# Filters.net
KiCad netlist of a schematic drawn in Altium Designer
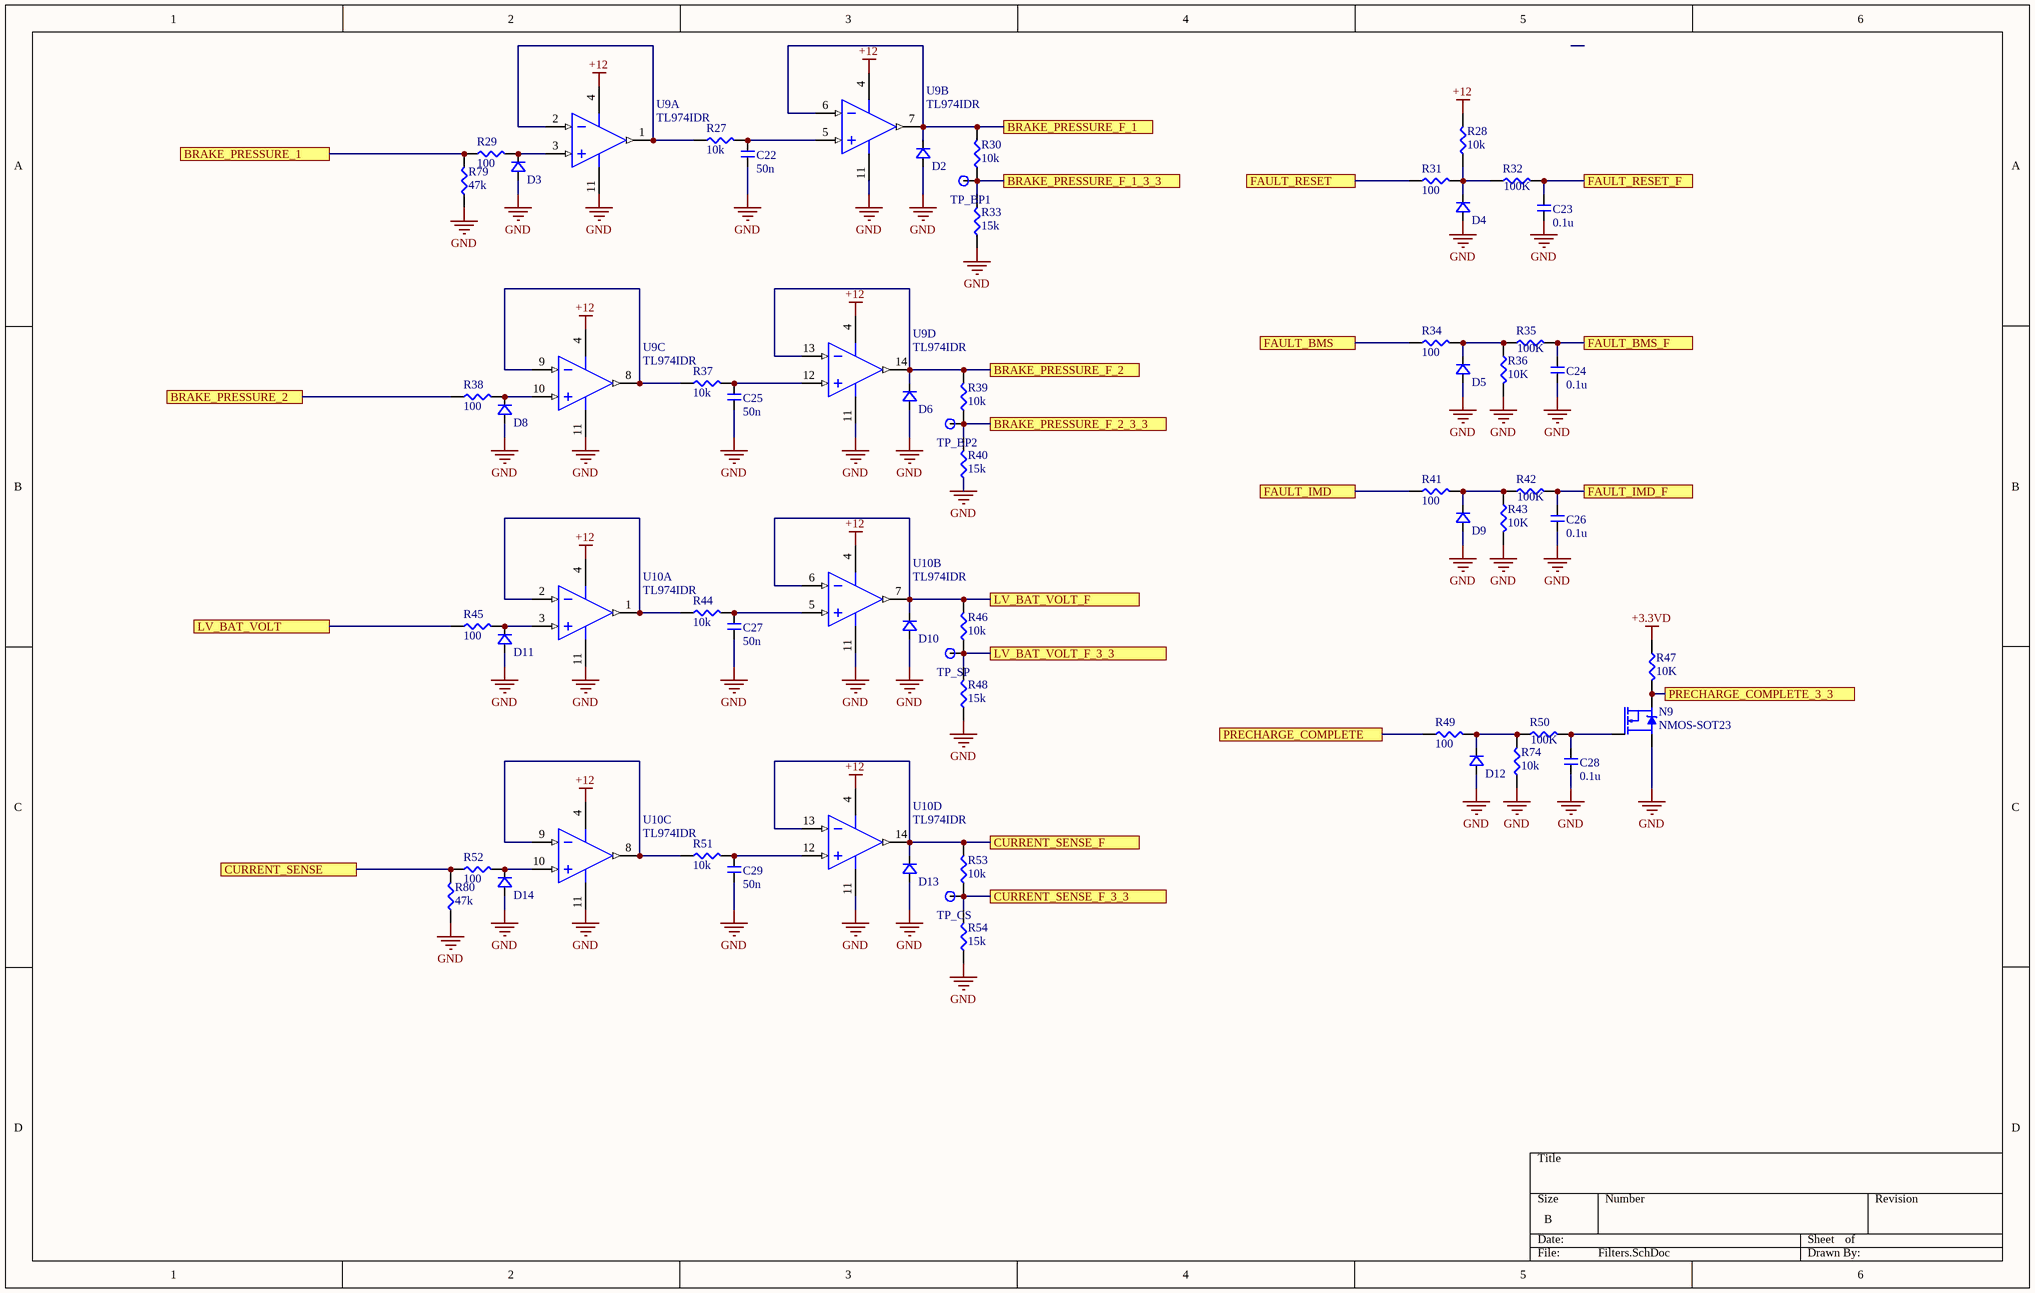
[diagram p0: Filters.SchDoc]

(export (version "E")
  (design (tool "Eeschema 10.0.6"))
  (components
    (comp (ref "C22")
      (value "50n")
      (footprint "CAP-0603")
      (libsource (lib "ife19_Elec_Library") (part "CAP-0603"))
    )
    (comp (ref "C23")
      (value "0.1u")
      (footprint "CAP-0603")
      (libsource (lib "ife19_Elec_Library") (part "CAP-0603"))
    )
    (comp (ref "C24")
      (value "0.1u")
      (footprint "CAP-0603")
      (libsource (lib "ife19_Elec_Library") (part "CAP-0603"))
    )
    (comp (ref "C25")
      (value "50n")
      (footprint "CAP-0603")
      (libsource (lib "ife19_Elec_Library") (part "CAP-0603"))
    )
    (comp (ref "C26")
      (value "0.1u")
      (footprint "CAP-0603")
      (libsource (lib "ife19_Elec_Library") (part "CAP-0603"))
    )
    (comp (ref "C27")
      (value "50n")
      (footprint "CAP-0603")
      (libsource (lib "ife19_Elec_Library") (part "CAP-0603"))
    )
    (comp (ref "C28")
      (value "0.1u")
      (footprint "CAP-0603")
      (libsource (lib "ife19_Elec_Library") (part "CAP-0603"))
    )
    (comp (ref "C29")
      (value "50n")
      (footprint "CAP-0603")
      (libsource (lib "ife19_Elec_Library") (part "CAP-0603"))
    )
    (comp (ref "D2")
      (value "5V ZENER")
      (footprint "SOD123")
      (libsource (lib "ife19_Elec_Library") (part "DIODE-SOD123"))
    )
    (comp (ref "D3")
      (value "12V ZENER")
      (footprint "ife19_Elec_Library:SOD123")
      (libsource (lib "ife19_Elec_Library") (part "DIODE-SOD123"))
    )
    (comp (ref "D4")
      (value "12V ZENER")
      (footprint "SOD123")
      (libsource (lib "ife19_Elec_Library") (part "DIODE-SOD123"))
    )
    (comp (ref "D5")
      (value "12V ZENER")
      (footprint "SOD123")
      (libsource (lib "ife19_Elec_Library") (part "DIODE-SOD123"))
    )
    (comp (ref "D6")
      (value "5V ZENER")
      (footprint "SOD123")
      (libsource (lib "ife19_Elec_Library") (part "DIODE-SOD123"))
    )
    (comp (ref "D8")
      (value "12V ZENER")
      (footprint "SOD123")
      (libsource (lib "ife19_Elec_Library") (part "DIODE-SOD123"))
    )
    (comp (ref "D9")
      (value "12V ZENER")
      (footprint "SOD123")
      (libsource (lib "ife19_Elec_Library") (part "DIODE-SOD123"))
    )
    (comp (ref "D10")
      (value "5V ZENER")
      (footprint "SOD123")
      (libsource (lib "ife19_Elec_Library") (part "DIODE-SOD123"))
    )
    (comp (ref "D11")
      (value "12V ZENER")
      (footprint "SOD123")
      (libsource (lib "ife19_Elec_Library") (part "DIODE-SOD123"))
    )
    (comp (ref "D12")
      (value "12V ZENER")
      (footprint "SOD123")
      (libsource (lib "ife19_Elec_Library") (part "DIODE-SOD123"))
    )
    (comp (ref "D13")
      (value "5V ZENER")
      (footprint "SOD123")
      (libsource (lib "ife19_Elec_Library") (part "DIODE-SOD123"))
    )
    (comp (ref "D14")
      (value "12V ZENER")
      (footprint "SOD123")
      (libsource (lib "ife19_Elec_Library") (part "DIODE-SOD123"))
    )
    (comp (ref "N9")
      (value "NMOS-SOT23")
      (footprint "SOT23")
      (libsource (lib "ife19_Elec_Library") (part "NMOS-SOT23"))
    )
    (comp (ref "R27")
      (value "10k")
      (footprint "RES-0603")
      (libsource (lib "ife19_Elec_Library") (part "RES-0603"))
    )
    (comp (ref "R28")
      (value "10k")
      (footprint "RES-0603")
      (libsource (lib "ife19_Elec_Library") (part "RES-0603"))
    )
    (comp (ref "R29")
      (value "100")
      (footprint "RES-0603")
      (libsource (lib "ife19_Elec_Library") (part "RES-0603"))
    )
    (comp (ref "R30")
      (value "10k")
      (footprint "RES-0603")
      (libsource (lib "ife19_Elec_Library") (part "RES-0603"))
    )
    (comp (ref "R31")
      (value "100")
      (footprint "RES-0603")
      (libsource (lib "ife19_Elec_Library") (part "RES-0603"))
    )
    (comp (ref "R32")
      (value "100K")
      (footprint "RES-0603")
      (libsource (lib "ife19_Elec_Library") (part "RES-0603"))
    )
    (comp (ref "R33")
      (value "15k")
      (footprint "RES-0603")
      (libsource (lib "ife19_Elec_Library") (part "RES-0603"))
    )
    (comp (ref "R34")
      (value "100")
      (footprint "RES-0603")
      (libsource (lib "ife19_Elec_Library") (part "RES-0603"))
    )
    (comp (ref "R35")
      (value "100K")
      (footprint "RES-0603")
      (libsource (lib "ife19_Elec_Library") (part "RES-0603"))
    )
    (comp (ref "R36")
      (value "10K")
      (footprint "RES-0603")
      (libsource (lib "ife19_Elec_Library") (part "RES-0603"))
    )
    (comp (ref "R37")
      (value "10k")
      (footprint "RES-0603")
      (libsource (lib "ife19_Elec_Library") (part "RES-0603"))
    )
    (comp (ref "R38")
      (value "100")
      (footprint "RES-0603")
      (libsource (lib "ife19_Elec_Library") (part "RES-0603"))
    )
    (comp (ref "R39")
      (value "10k")
      (footprint "RES-0603")
      (libsource (lib "ife19_Elec_Library") (part "RES-0603"))
    )
    (comp (ref "R40")
      (value "15k")
      (footprint "RES-0603")
      (libsource (lib "ife19_Elec_Library") (part "RES-0603"))
    )
    (comp (ref "R41")
      (value "100")
      (footprint "RES-0603")
      (libsource (lib "ife19_Elec_Library") (part "RES-0603"))
    )
    (comp (ref "R42")
      (value "100K")
      (footprint "RES-0603")
      (libsource (lib "ife19_Elec_Library") (part "RES-0603"))
    )
    (comp (ref "R43")
      (value "10K")
      (footprint "RES-0603")
      (libsource (lib "ife19_Elec_Library") (part "RES-0603"))
    )
    (comp (ref "R44")
      (value "10k")
      (footprint "RES-0603")
      (libsource (lib "ife19_Elec_Library") (part "RES-0603"))
    )
    (comp (ref "R45")
      (value "100")
      (footprint "RES-0603")
      (libsource (lib "ife19_Elec_Library") (part "RES-0603"))
    )
    (comp (ref "R46")
      (value "10k")
      (footprint "RES-0603")
      (libsource (lib "ife19_Elec_Library") (part "RES-0603"))
    )
    (comp (ref "R47")
      (value "10K")
      (footprint "RES-0603")
      (libsource (lib "ife19_Elec_Library") (part "RES-0603"))
    )
    (comp (ref "R48")
      (value "15k")
      (footprint "RES-0603")
      (libsource (lib "ife19_Elec_Library") (part "RES-0603"))
    )
    (comp (ref "R49")
      (value "100")
      (footprint "RES-0603")
      (libsource (lib "ife19_Elec_Library") (part "RES-0603"))
    )
    (comp (ref "R50")
      (value "100K")
      (footprint "RES-0603")
      (libsource (lib "ife19_Elec_Library") (part "RES-0603"))
    )
    (comp (ref "R51")
      (value "10k")
      (footprint "RES-0603")
      (libsource (lib "ife19_Elec_Library") (part "RES-0603"))
    )
    (comp (ref "R52")
      (value "100")
      (footprint "RES-0603")
      (libsource (lib "ife19_Elec_Library") (part "RES-0603"))
    )
    (comp (ref "R53")
      (value "10k")
      (footprint "RES-0603")
      (libsource (lib "ife19_Elec_Library") (part "RES-0603"))
    )
    (comp (ref "R54")
      (value "15k")
      (footprint "RES-0603")
      (libsource (lib "ife19_Elec_Library") (part "RES-0603"))
    )
    (comp (ref "R74")
      (value "10k")
      (footprint "RES-0603")
      (libsource (lib "ife19_Elec_Library") (part "RES-0603"))
    )
    (comp (ref "R79")
      (value "47k")
      (footprint "RES-0603")
      (libsource (lib "ife19_Elec_Library") (part "RES-0603"))
    )
    (comp (ref "R80")
      (value "47k")
      (footprint "RES-0603")
      (libsource (lib "ife19_Elec_Library") (part "RES-0603"))
    )
    (comp (ref "TP_BP1")
      (value "~")
      (footprint "Testpoint")
      (libsource (lib "ife19_Elec_Library") (part "Testpoint"))
    )
    (comp (ref "TP_BP2")
      (value "~")
      (footprint "Testpoint")
      (libsource (lib "ife19_Elec_Library") (part "Testpoint"))
    )
    (comp (ref "TP_CS")
      (value "~")
      (footprint "Testpoint")
      (libsource (lib "ife19_Elec_Library") (part "Testpoint"))
    )
    (comp (ref "TP_SP")
      (value "~")
      (footprint "Testpoint")
      (libsource (lib "ife19_Elec_Library") (part "Testpoint"))
    )
    (comp (ref "U9")
      (value "TL974IDR")
      (footprint "D0014A_M")
      (fields (field (name "MANUFACTURER") "Texas Instruments"))
      (libsource (lib "Altium Content Vault") (part "TI-TLXX4X_MC3403-X14"))
    )
    (comp (ref "U10")
      (value "TL974IDR")
      (footprint "D0014A_M")
      (fields (field (name "MANUFACTURER") "Texas Instruments"))
      (libsource (lib "Altium Content Vault") (part "TI-TLXX4X_MC3403-X14"))
    )
  )
  (nets
    (net (code "1") (name "+3.3VD") (class "Default")
      (node (ref "R47") (pin "1") (pinfunction "1_1") (pintype "passive"))
    )
    (net (code "2") (name "+12") (class "Default")
      (node (ref "R28") (pin "2") (pinfunction "2_2") (pintype "passive"))
      (node (ref "U10") (pin "4") (pinfunction "VCC+_4") (pintype "power_in"))
      (node (ref "U9") (pin "4") (pinfunction "VCC+_4") (pintype "power_in"))
    )
    (net (code "3") (name "/BRAKE_PRESSURE_1") (class "Default")
      (node (ref "R29") (pin "1") (pinfunction "1_1") (pintype "passive"))
      (node (ref "R79") (pin "2") (pinfunction "2_2") (pintype "passive"))
    )
    (net (code "4") (name "/BRAKE_PRESSURE_2") (class "Default")
      (node (ref "R38") (pin "1") (pinfunction "1_1") (pintype "passive"))
    )
    (net (code "5") (name "/BRAKE_PRESSURE_F_1") (class "Default")
      (node (ref "D2") (pin "K") (pinfunction "K_K") (pintype "passive"))
      (node (ref "R30") (pin "2") (pinfunction "2_2") (pintype "passive"))
      (node (ref "U9") (pin "6") (pinfunction "IN2-_6") (pintype "input"))
      (node (ref "U9") (pin "7") (pinfunction "OUT2_7") (pintype "output"))
    )
    (net (code "6") (name "/BRAKE_PRESSURE_F_1_3_3") (class "Default")
      (node (ref "R30") (pin "1") (pinfunction "1_1") (pintype "passive"))
      (node (ref "R33") (pin "2") (pinfunction "2_2") (pintype "passive"))
      (node (ref "TP_BP1") (pin "1") (pinfunction "1_1") (pintype "passive"))
    )
    (net (code "7") (name "/BRAKE_PRESSURE_F_2") (class "Default")
      (node (ref "D6") (pin "K") (pinfunction "K_K") (pintype "passive"))
      (node (ref "R39") (pin "2") (pinfunction "2_2") (pintype "passive"))
      (node (ref "U9") (pin "13") (pinfunction "IN4-_13") (pintype "input"))
      (node (ref "U9") (pin "14") (pinfunction "OUT4_14") (pintype "output"))
    )
    (net (code "8") (name "/BRAKE_PRESSURE_F_2_3_3") (class "Default")
      (node (ref "R39") (pin "1") (pinfunction "1_1") (pintype "passive"))
      (node (ref "R40") (pin "2") (pinfunction "2_2") (pintype "passive"))
      (node (ref "TP_BP2") (pin "1") (pinfunction "1_1") (pintype "passive"))
    )
    (net (code "9") (name "/CURRENT_SENSE") (class "Default")
      (node (ref "R52") (pin "1") (pinfunction "1_1") (pintype "passive"))
      (node (ref "R80") (pin "2") (pinfunction "2_2") (pintype "passive"))
    )
    (net (code "10") (name "/CURRENT_SENSE_F") (class "Default")
      (node (ref "D13") (pin "K") (pinfunction "K_K") (pintype "passive"))
      (node (ref "R53") (pin "2") (pinfunction "2_2") (pintype "passive"))
      (node (ref "U10") (pin "13") (pinfunction "IN4-_13") (pintype "input"))
      (node (ref "U10") (pin "14") (pinfunction "OUT4_14") (pintype "output"))
    )
    (net (code "11") (name "/CURRENT_SENSE_F_3_3") (class "Default")
      (node (ref "R53") (pin "1") (pinfunction "1_1") (pintype "passive"))
      (node (ref "R54") (pin "2") (pinfunction "2_2") (pintype "passive"))
      (node (ref "TP_CS") (pin "1") (pinfunction "1_1") (pintype "passive"))
    )
    (net (code "12") (name "/FAULT_BMS") (class "Default")
      (node (ref "R34") (pin "1") (pinfunction "1_1") (pintype "passive"))
    )
    (net (code "13") (name "/FAULT_BMS_F") (class "Default")
      (node (ref "C24") (pin "2") (pinfunction "2_2") (pintype "passive"))
      (node (ref "R35") (pin "2") (pinfunction "2_2") (pintype "passive"))
    )
    (net (code "14") (name "/FAULT_IMD") (class "Default")
      (node (ref "R41") (pin "1") (pinfunction "1_1") (pintype "passive"))
    )
    (net (code "15") (name "/FAULT_IMD_F") (class "Default")
      (node (ref "C26") (pin "2") (pinfunction "2_2") (pintype "passive"))
      (node (ref "R42") (pin "2") (pinfunction "2_2") (pintype "passive"))
    )
    (net (code "16") (name "/FAULT_RESET") (class "Default")
      (node (ref "R31") (pin "1") (pinfunction "1_1") (pintype "passive"))
    )
    (net (code "17") (name "/FAULT_RESET_F") (class "Default")
      (node (ref "C23") (pin "2") (pinfunction "2_2") (pintype "passive"))
      (node (ref "R32") (pin "2") (pinfunction "2_2") (pintype "passive"))
    )
    (net (code "18") (name "/LV_BAT_VOLT") (class "Default")
      (node (ref "R45") (pin "1") (pinfunction "1_1") (pintype "passive"))
    )
    (net (code "19") (name "/LV_BAT_VOLT_F") (class "Default")
      (node (ref "D10") (pin "K") (pinfunction "K_K") (pintype "passive"))
      (node (ref "R46") (pin "2") (pinfunction "2_2") (pintype "passive"))
      (node (ref "U10") (pin "6") (pinfunction "IN2-_6") (pintype "input"))
      (node (ref "U10") (pin "7") (pinfunction "OUT2_7") (pintype "output"))
    )
    (net (code "20") (name "/LV_BAT_VOLT_F_3_3") (class "Default")
      (node (ref "R46") (pin "1") (pinfunction "1_1") (pintype "passive"))
      (node (ref "R48") (pin "2") (pinfunction "2_2") (pintype "passive"))
      (node (ref "TP_SP") (pin "1") (pinfunction "1_1") (pintype "passive"))
    )
    (net (code "21") (name "/PRECHARGE_COMPLETE") (class "Default")
      (node (ref "R49") (pin "1") (pinfunction "1_1") (pintype "passive"))
    )
    (net (code "22") (name "/PRECHARGE_COMPLETE_3_3") (class "Default")
      (node (ref "N9") (pin "3") (pinfunction "D_3") (pintype "passive"))
      (node (ref "R47") (pin "2") (pinfunction "2_2") (pintype "passive"))
    )
    (net (code "23") (name "GND") (class "Default")
      (node (ref "C22") (pin "1") (pinfunction "1_1") (pintype "passive"))
      (node (ref "C23") (pin "1") (pinfunction "1_1") (pintype "passive"))
      (node (ref "C24") (pin "1") (pinfunction "1_1") (pintype "passive"))
      (node (ref "C25") (pin "1") (pinfunction "1_1") (pintype "passive"))
      (node (ref "C26") (pin "1") (pinfunction "1_1") (pintype "passive"))
      (node (ref "C27") (pin "1") (pinfunction "1_1") (pintype "passive"))
      (node (ref "C28") (pin "1") (pinfunction "1_1") (pintype "passive"))
      (node (ref "C29") (pin "1") (pinfunction "1_1") (pintype "passive"))
      (node (ref "D10") (pin "A") (pinfunction "A_A") (pintype "passive"))
      (node (ref "D11") (pin "A") (pinfunction "A_A") (pintype "passive"))
      (node (ref "D12") (pin "A") (pinfunction "A_A") (pintype "passive"))
      (node (ref "D13") (pin "A") (pinfunction "A_A") (pintype "passive"))
      (node (ref "D14") (pin "A") (pinfunction "A_A") (pintype "passive"))
      (node (ref "D2") (pin "A") (pinfunction "A_A") (pintype "passive"))
      (node (ref "D3") (pin "A") (pinfunction "A_A") (pintype "passive"))
      (node (ref "D4") (pin "A") (pinfunction "A_A") (pintype "passive"))
      (node (ref "D5") (pin "A") (pinfunction "A_A") (pintype "passive"))
      (node (ref "D6") (pin "A") (pinfunction "A_A") (pintype "passive"))
      (node (ref "D8") (pin "A") (pinfunction "A_A") (pintype "passive"))
      (node (ref "D9") (pin "A") (pinfunction "A_A") (pintype "passive"))
      (node (ref "N9") (pin "2") (pinfunction "S_2") (pintype "passive"))
      (node (ref "R33") (pin "1") (pinfunction "1_1") (pintype "passive"))
      (node (ref "R36") (pin "2") (pinfunction "2_2") (pintype "passive"))
      (node (ref "R40") (pin "1") (pinfunction "1_1") (pintype "passive"))
      (node (ref "R43") (pin "2") (pinfunction "2_2") (pintype "passive"))
      (node (ref "R48") (pin "1") (pinfunction "1_1") (pintype "passive"))
      (node (ref "R54") (pin "1") (pinfunction "1_1") (pintype "passive"))
      (node (ref "R74") (pin "1") (pinfunction "1_1") (pintype "passive"))
      (node (ref "R79") (pin "1") (pinfunction "1_1") (pintype "passive"))
      (node (ref "R80") (pin "1") (pinfunction "1_1") (pintype "passive"))
      (node (ref "U10") (pin "11") (pinfunction "VCC-_11") (pintype "power_in"))
      (node (ref "U9") (pin "11") (pinfunction "VCC-_11") (pintype "power_in"))
    )
    (net (code "24") (name "Net-(D4-PadK)") (class "Default")
      (node (ref "D4") (pin "K") (pinfunction "K_K") (pintype "passive"))
      (node (ref "R28") (pin "1") (pinfunction "1_1") (pintype "passive"))
      (node (ref "R31") (pin "2") (pinfunction "2_2") (pintype "passive"))
      (node (ref "R32") (pin "1") (pinfunction "1_1") (pintype "passive"))
    )
    (net (code "25") (name "Net-(D5-PadK)") (class "Default")
      (node (ref "D5") (pin "K") (pinfunction "K_K") (pintype "passive"))
      (node (ref "R34") (pin "2") (pinfunction "2_2") (pintype "passive"))
      (node (ref "R35") (pin "1") (pinfunction "1_1") (pintype "passive"))
      (node (ref "R36") (pin "1") (pinfunction "1_1") (pintype "passive"))
    )
    (net (code "26") (name "Net-(D9-PadK)") (class "Default")
      (node (ref "D9") (pin "K") (pinfunction "K_K") (pintype "passive"))
      (node (ref "R41") (pin "2") (pinfunction "2_2") (pintype "passive"))
      (node (ref "R42") (pin "1") (pinfunction "1_1") (pintype "passive"))
      (node (ref "R43") (pin "1") (pinfunction "1_1") (pintype "passive"))
    )
    (net (code "27") (name "Net-(D12-PadK)") (class "Default")
      (node (ref "D12") (pin "K") (pinfunction "K_K") (pintype "passive"))
      (node (ref "R49") (pin "2") (pinfunction "2_2") (pintype "passive"))
      (node (ref "R50") (pin "1") (pinfunction "1_1") (pintype "passive"))
      (node (ref "R74") (pin "2") (pinfunction "2_2") (pintype "passive"))
    )
    (net (code "28") (name "Net-(N9-G)") (class "Default")
      (node (ref "C28") (pin "2") (pinfunction "2_2") (pintype "passive"))
      (node (ref "N9") (pin "1") (pinfunction "G_1") (pintype "passive"))
      (node (ref "R50") (pin "2") (pinfunction "2_2") (pintype "passive"))
    )
    (net (code "29") (name "Net-(U9A-IN1+)") (class "Default")
      (node (ref "D3") (pin "K") (pinfunction "K_K") (pintype "passive"))
      (node (ref "R29") (pin "2") (pinfunction "2_2") (pintype "passive"))
      (node (ref "U9") (pin "3") (pinfunction "IN1+_3") (pintype "input"))
    )
    (net (code "30") (name "Net-(U9A-IN1-)") (class "Default")
      (node (ref "R27") (pin "1") (pinfunction "1_1") (pintype "passive"))
      (node (ref "U9") (pin "1") (pinfunction "OUT1_1") (pintype "output"))
      (node (ref "U9") (pin "2") (pinfunction "IN1-_2") (pintype "input"))
    )
    (net (code "31") (name "Net-(U9B-IN2+)") (class "Default")
      (node (ref "C22") (pin "2") (pinfunction "2_2") (pintype "passive"))
      (node (ref "R27") (pin "2") (pinfunction "2_2") (pintype "passive"))
      (node (ref "U9") (pin "5") (pinfunction "IN2+_5") (pintype "input"))
    )
    (net (code "32") (name "Net-(U9C-IN3+)") (class "Default")
      (node (ref "D8") (pin "K") (pinfunction "K_K") (pintype "passive"))
      (node (ref "R38") (pin "2") (pinfunction "2_2") (pintype "passive"))
      (node (ref "U9") (pin "10") (pinfunction "IN3+_10") (pintype "input"))
    )
    (net (code "33") (name "Net-(U9C-IN3-)") (class "Default")
      (node (ref "R37") (pin "1") (pinfunction "1_1") (pintype "passive"))
      (node (ref "U9") (pin "8") (pinfunction "OUT3_8") (pintype "output"))
      (node (ref "U9") (pin "9") (pinfunction "IN3-_9") (pintype "input"))
    )
    (net (code "34") (name "Net-(U9D-IN4+)") (class "Default")
      (node (ref "C25") (pin "2") (pinfunction "2_2") (pintype "passive"))
      (node (ref "R37") (pin "2") (pinfunction "2_2") (pintype "passive"))
      (node (ref "U9") (pin "12") (pinfunction "IN4+_12") (pintype "input"))
    )
    (net (code "35") (name "Net-(U10A-IN1+)") (class "Default")
      (node (ref "D11") (pin "K") (pinfunction "K_K") (pintype "passive"))
      (node (ref "R45") (pin "2") (pinfunction "2_2") (pintype "passive"))
      (node (ref "U10") (pin "3") (pinfunction "IN1+_3") (pintype "input"))
    )
    (net (code "36") (name "Net-(U10A-IN1-)") (class "Default")
      (node (ref "R44") (pin "1") (pinfunction "1_1") (pintype "passive"))
      (node (ref "U10") (pin "1") (pinfunction "OUT1_1") (pintype "output"))
      (node (ref "U10") (pin "2") (pinfunction "IN1-_2") (pintype "input"))
    )
    (net (code "37") (name "Net-(U10B-IN2+)") (class "Default")
      (node (ref "C27") (pin "2") (pinfunction "2_2") (pintype "passive"))
      (node (ref "R44") (pin "2") (pinfunction "2_2") (pintype "passive"))
      (node (ref "U10") (pin "5") (pinfunction "IN2+_5") (pintype "input"))
    )
    (net (code "38") (name "Net-(U10C-IN3+)") (class "Default")
      (node (ref "D14") (pin "K") (pinfunction "K_K") (pintype "passive"))
      (node (ref "R52") (pin "2") (pinfunction "2_2") (pintype "passive"))
      (node (ref "U10") (pin "10") (pinfunction "IN3+_10") (pintype "input"))
    )
    (net (code "39") (name "Net-(U10C-IN3-)") (class "Default")
      (node (ref "R51") (pin "1") (pinfunction "1_1") (pintype "passive"))
      (node (ref "U10") (pin "8") (pinfunction "OUT3_8") (pintype "output"))
      (node (ref "U10") (pin "9") (pinfunction "IN3-_9") (pintype "input"))
    )
    (net (code "40") (name "Net-(U10D-IN4+)") (class "Default")
      (node (ref "C29") (pin "2") (pinfunction "2_2") (pintype "passive"))
      (node (ref "R51") (pin "2") (pinfunction "2_2") (pintype "passive"))
      (node (ref "U10") (pin "12") (pinfunction "IN4+_12") (pintype "input"))
    )
  )
)
